# power_display.net
KiCad netlist of a schematic drawn in Altium Designer
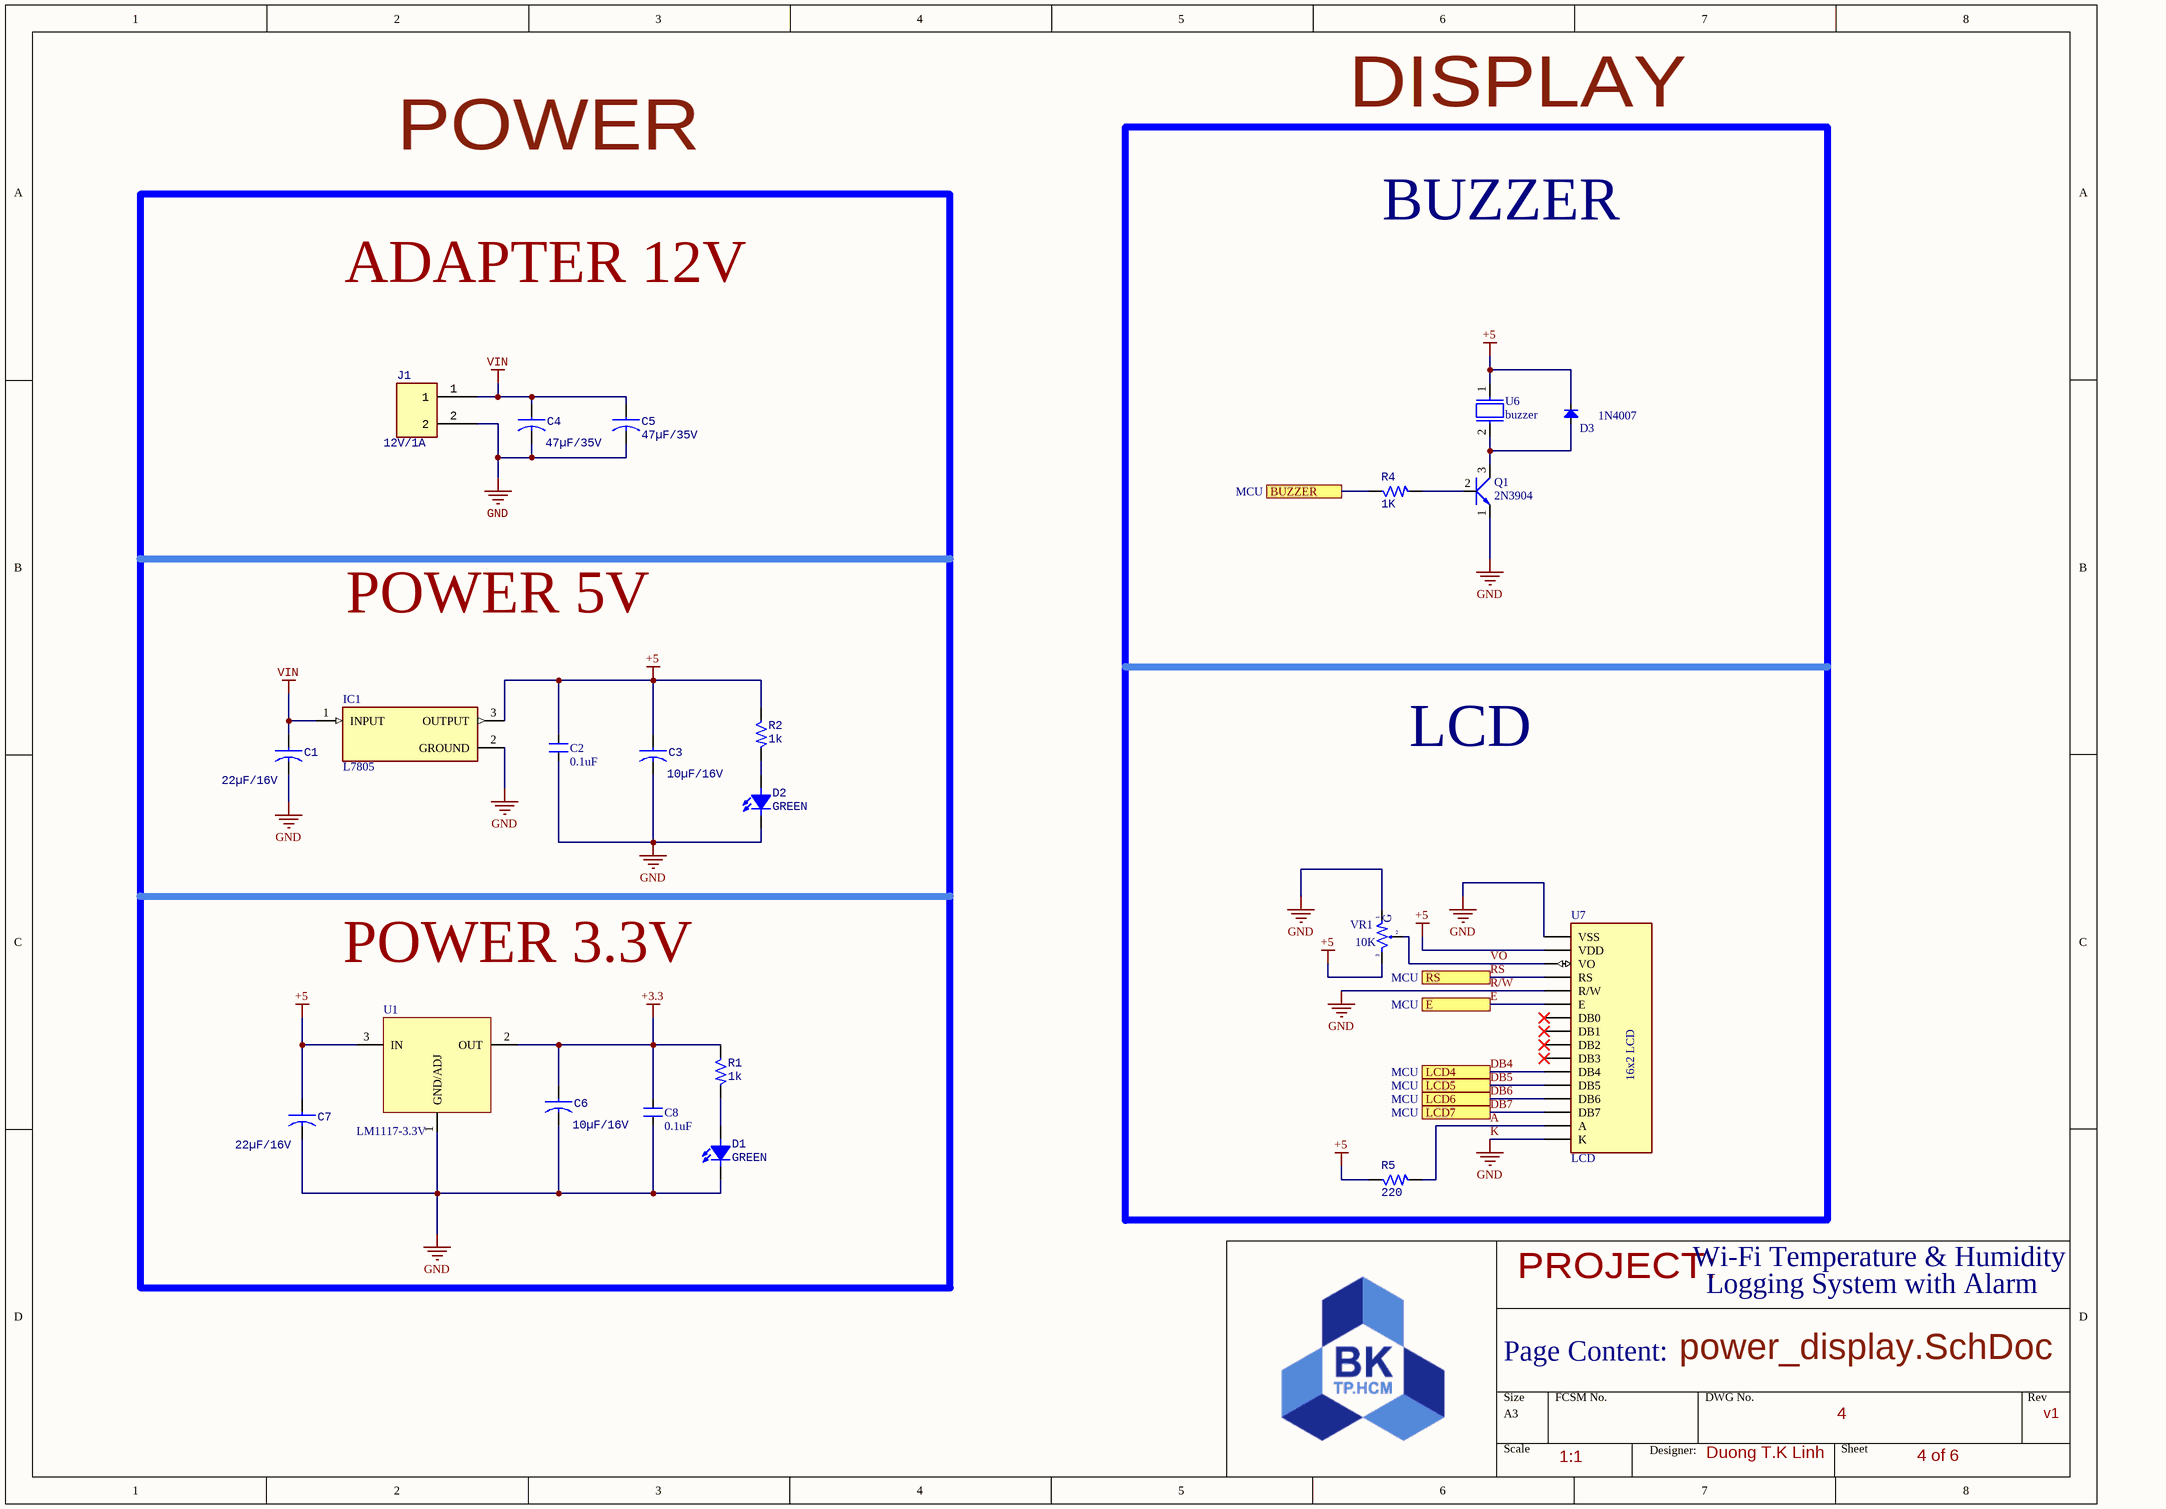
[diagram p0: power_display.SchDoc]

(export (version "E")
  (design (tool "Eeschema 10.0.6"))
  (components
    (comp (ref "C1") (value "22µF/16V") (footprint "CP1/2") (libsource (lib "Database") (part "CAP-ALU")))
    (comp (ref "C2")
      (value "0.1uF")
      (footprint "CN2")
      (description "Cap np 104 => 105pF")
      (libsource (lib "Compiled_Devzone") (part "CN2"))
    )
    (comp (ref "C3") (value "10µF/16V") (footprint "CP1/2") (libsource (lib "Database") (part "CAP-ALU")))
    (comp (ref "C4") (value "47µF/35V") (footprint "CP1/2") (libsource (lib "Database") (part "CAP-ALU")))
    (comp (ref "C5") (value "47µF/35V") (footprint "CP1/2") (libsource (lib "Database") (part "CAP-ALU")))
    (comp (ref "C6") (value "10µF/16V") (footprint "CP1/2") (libsource (lib "Database") (part "CAP-ALU")))
    (comp (ref "C7") (value "22µF/16V") (footprint "CP1/2") (libsource (lib "Database") (part "CAP-ALU")))
    (comp (ref "C8")
      (value "0.1uF")
      (footprint "CN2")
      (description "Cap np 104 => 105pF")
      (libsource (lib "Compiled_Devzone") (part "CN2"))
    )
    (comp (ref "D1")
      (value "GREEN")
      (footprint "LED-5TRED")
      (description "Green 569nm LED Indication - Discrete 2.1V 0603 (1608 Metric)")
      (libsource (lib "Database") (part "LED"))
    )
    (comp (ref "D2")
      (value "GREEN")
      (footprint "LED-5TRED")
      (description "Green 569nm LED Indication - Discrete 2.1V 0603 (1608 Metric)")
      (libsource (lib "Database") (part "LED"))
    )
    (comp (ref "D3")
      (value "Diode")
      (footprint "DIO-1A")
      (description "Default Diode")
      (fields (field (name "PUBLISHER") "Altium Limited"))
      (libsource (lib "Altium Library") (part "Diode"))
    )
    (comp (ref "IC1") (value "L7805") (footprint "L7805") (libsource (lib "Schlib1") (part "L7805")))
    (comp (ref "J1")
      (value "12V/1A")
      (footprint "J2-D1T")
      (description "2 Position Wire to Board Terminal Block Horizontal with Board 0.200\" (5.08mm) Through Hole")
      (libsource (lib "Database") (part "BOARD TERMINAL 2POS"))
    )
    (comp (ref "Q1")
      (value "2N3904")
      (footprint "TO92-123")
      (description "NPN 600mW, ECB")
      (libsource (lib "Altium Library") (part "2N904"))
    )
    (comp (ref "R1") (value "1k") (footprint "RES-1/4W-SMALL") (libsource (lib "ID") (part "RES-SMD")))
    (comp (ref "R2") (value "1k") (footprint "RES-1/4W-SMALL") (libsource (lib "ID") (part "RES-SMD")))
    (comp (ref "R4") (value "1K") (footprint "RES-1/4W-SMALL") (libsource (lib "ID") (part "RES-SMD")))
    (comp (ref "R5") (value "220") (footprint "RES-1/4W-SMALL") (libsource (lib "ID") (part "RES-SMD")))
    (comp (ref "U1")
      (value "LM1117-3.3V")
      (footprint "TO220-123")
      (description "Low-Dropout Linear Regulator")
      (fields (field (name "CREATOR") "Nguyen Ba Bien"))
      (libsource (lib "KhanhBK_Library_4") (part "LM1117"))
    )
    (comp (ref "U6") (value "buzzer") (footprint "buzzer") (libsource (lib "Schlib1") (part "buzzer")))
    (comp (ref "U7") (value "LCD") (footprint "LCD") (libsource (lib "Schlib1") (part "LCD")))
    (comp (ref "VR1")
      (value "10K")
      (footprint "VR-S1")
      (description "Var Resistor")
      (libsource (lib "Altium Library") (part "VR-S"))
    )
  )
  (nets
    (net (code "1") (name "+3.3") (class "Default")
      (node (ref "C6") (pin "1") (pinfunction "1_1") (pintype "passive"))
      (node (ref "C8") (pin "2") (pinfunction "2_2") (pintype "passive"))
      (node (ref "R1") (pin "1") (pinfunction "1_1") (pintype "passive"))
      (node (ref "U1") (pin "2") (pinfunction "OUT_2") (pintype "passive"))
    )
    (net (code "2") (name "+5") (class "Default")
      (node (ref "C2") (pin "2") (pinfunction "2_2") (pintype "passive"))
      (node (ref "C3") (pin "1") (pinfunction "1_1") (pintype "passive"))
      (node (ref "C7") (pin "1") (pinfunction "1_1") (pintype "passive"))
      (node (ref "D3") (pin "2") (pinfunction "K_2") (pintype "passive"))
      (node (ref "IC1") (pin "3") (pinfunction "OUTPUT_3") (pintype "output"))
      (node (ref "R2") (pin "1") (pinfunction "1_1") (pintype "passive"))
      (node (ref "R5") (pin "1") (pinfunction "1_1") (pintype "passive"))
      (node (ref "U1") (pin "3") (pinfunction "IN_3") (pintype "passive"))
      (node (ref "U6") (pin "1") (pinfunction "1_1") (pintype "passive"))
      (node (ref "U7") (pin "2") (pinfunction "VDD_2") (pintype "passive"))
      (node (ref "VR1") (pin "3") (pinfunction "3_3") (pintype "passive"))
    )
    (net (code "3") (name "/A") (class "Default")
      (node (ref "R5") (pin "2") (pinfunction "2_2") (pintype "passive"))
      (node (ref "U7") (pin "15") (pinfunction "A_15") (pintype "power_in"))
    )
    (net (code "4") (name "/BUZZER") (class "Default")
      (node (ref "R4") (pin "1") (pinfunction "1_1") (pintype "passive"))
    )
    (net (code "5") (name "/DB4") (class "Default")
      (node (ref "U7") (pin "11") (pinfunction "DB4_11") (pintype "passive"))
    )
    (net (code "6") (name "/DB5") (class "Default")
      (node (ref "U7") (pin "12") (pinfunction "DB5_12") (pintype "passive"))
    )
    (net (code "7") (name "/DB6") (class "Default")
      (node (ref "U7") (pin "13") (pinfunction "DB6_13") (pintype "passive"))
    )
    (net (code "8") (name "/DB7") (class "Default")
      (node (ref "U7") (pin "14") (pinfunction "DB7_14") (pintype "passive"))
    )
    (net (code "9") (name "/E") (class "Default")
      (node (ref "U7") (pin "6") (pinfunction "E_6") (pintype "passive"))
    )
    (net (code "10") (name "/RS") (class "Default")
      (node (ref "U7") (pin "4") (pinfunction "RS_4") (pintype "passive"))
    )
    (net (code "11") (name "/VO") (class "Default")
      (node (ref "U7") (pin "3") (pinfunction "VO_3") (pintype "bidirectional"))
      (node (ref "VR1") (pin "2") (pinfunction "2_2") (pintype "passive"))
    )
    (net (code "12") (name "GND") (class "Default")
      (node (ref "C1") (pin "2") (pinfunction "2_2") (pintype "passive"))
      (node (ref "C2") (pin "1") (pinfunction "1_1") (pintype "passive"))
      (node (ref "C3") (pin "2") (pinfunction "2_2") (pintype "passive"))
      (node (ref "C4") (pin "2") (pinfunction "2_2") (pintype "passive"))
      (node (ref "C5") (pin "2") (pinfunction "2_2") (pintype "passive"))
      (node (ref "C6") (pin "2") (pinfunction "2_2") (pintype "passive"))
      (node (ref "C7") (pin "2") (pinfunction "2_2") (pintype "passive"))
      (node (ref "C8") (pin "1") (pinfunction "1_1") (pintype "passive"))
      (node (ref "D1") (pin "2") (pinfunction "K_2") (pintype "passive"))
      (node (ref "D2") (pin "2") (pinfunction "K_2") (pintype "passive"))
      (node (ref "IC1") (pin "2") (pinfunction "GROUND_2") (pintype "power_in"))
      (node (ref "J1") (pin "2") (pinfunction "2_2") (pintype "passive"))
      (node (ref "Q1") (pin "1") (pinfunction "E_1") (pintype "passive"))
      (node (ref "U1") (pin "1") (pinfunction "GND/ADJ_1") (pintype "passive"))
      (node (ref "U7") (pin "1") (pinfunction "VSS_1") (pintype "power_in"))
      (node (ref "U7") (pin "16") (pinfunction "K_16") (pintype "power_in"))
      (node (ref "U7") (pin "5") (pinfunction "R/W_5") (pintype "passive"))
      (node (ref "VR1") (pin "1") (pinfunction "1_1") (pintype "passive"))
    )
    (net (code "13") (name "Net-(D1-A)") (class "Default")
      (node (ref "D1") (pin "1") (pinfunction "A_1") (pintype "passive"))
      (node (ref "R1") (pin "2") (pinfunction "2_2") (pintype "passive"))
    )
    (net (code "14") (name "Net-(D2-A)") (class "Default")
      (node (ref "D2") (pin "1") (pinfunction "A_1") (pintype "passive"))
      (node (ref "R2") (pin "2") (pinfunction "2_2") (pintype "passive"))
    )
    (net (code "15") (name "Net-(D3-A)") (class "Default")
      (node (ref "D3") (pin "1") (pinfunction "A_1") (pintype "passive"))
      (node (ref "Q1") (pin "3") (pinfunction "C_3") (pintype "passive"))
      (node (ref "U6") (pin "2") (pinfunction "2_2") (pintype "passive"))
    )
    (net (code "16") (name "Net-(Q1-B)") (class "Default")
      (node (ref "Q1") (pin "2") (pinfunction "B_2") (pintype "passive"))
      (node (ref "R4") (pin "2") (pinfunction "2_2") (pintype "passive"))
    )
    (net (code "17") (name "VIN") (class "Default")
      (node (ref "C1") (pin "1") (pinfunction "1_1") (pintype "passive"))
      (node (ref "C4") (pin "1") (pinfunction "1_1") (pintype "passive"))
      (node (ref "C5") (pin "1") (pinfunction "1_1") (pintype "passive"))
      (node (ref "IC1") (pin "1") (pinfunction "INPUT_1") (pintype "input"))
      (node (ref "J1") (pin "1") (pinfunction "1_1") (pintype "passive"))
    )
    (net (code "18") (name "unconnected-(U7-DB0-Pad7)") (class "Default")
      (node (ref "U7") (pin "7") (pinfunction "DB0_7") (pintype "passive+no_connect"))
    )
    (net (code "19") (name "unconnected-(U7-DB1-Pad8)") (class "Default")
      (node (ref "U7") (pin "8") (pinfunction "DB1_8") (pintype "passive+no_connect"))
    )
    (net (code "20") (name "unconnected-(U7-DB2-Pad9)") (class "Default")
      (node (ref "U7") (pin "9") (pinfunction "DB2_9") (pintype "passive+no_connect"))
    )
    (net (code "21") (name "unconnected-(U7-DB3-Pad10)") (class "Default")
      (node (ref "U7") (pin "10") (pinfunction "DB3_10") (pintype "passive+no_connect"))
    )
  )
)
